# 3V3_LDO.net
KiCad netlist of a schematic drawn in Altium Designer
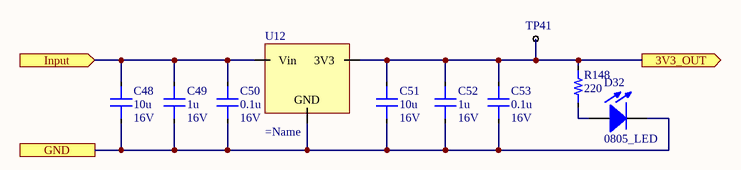
[diagram p0: 3V3_LDO.SchDoc]

(export (version "E")
  (design (tool "Eeschema 10.0.6"))
  (components
    (comp (ref "C48")
      (value "10u")
      (footprint "0805_CAP")
      (fields (field (name "VOLTAGE") "16V") (field (name "Comment") "Capacitor"))
      (libsource (lib "Capacitors") (part "Capacitor"))
    )
    (comp (ref "C49")
      (value "1u")
      (footprint "0603_CAP")
      (fields (field (name "VOLTAGE") "16V") (field (name "Comment") "Capacitor"))
      (libsource (lib "Capacitors") (part "Capacitor"))
    )
    (comp (ref "C50")
      (value "0.1u")
      (footprint "0805_CAP")
      (fields (field (name "VOLTAGE") "16V") (field (name "Comment") "Capacitor"))
      (libsource (lib "Capacitors") (part "Capacitor"))
    )
    (comp (ref "C51")
      (value "10u")
      (footprint "0805_CAP")
      (fields (field (name "VOLTAGE") "16V") (field (name "Comment") "Capacitor"))
      (libsource (lib "Capacitors") (part "Capacitor"))
    )
    (comp (ref "C52")
      (value "1u")
      (footprint "0805_CAP")
      (fields (field (name "VOLTAGE") "16V") (field (name "Comment") "Capacitor"))
      (libsource (lib "Capacitors") (part "Capacitor"))
    )
    (comp (ref "C53")
      (value "0.1u")
      (footprint "0805_CAP")
      (fields (field (name "VOLTAGE") "16V") (field (name "Comment") "Capacitor"))
      (libsource (lib "Capacitors") (part "Capacitor"))
    )
    (comp (ref "D32")
      (value "0805_LED")
      (footprint "0805_LED")
      (description "Generic 0805 LED")
      (libsource (lib "Diodes") (part "0805_LED"))
    )
    (comp (ref "R148")
      (value "220")
      (footprint "0603_RES")
      (fields (field (name "Comment") "Resistor"))
      (libsource (lib "Resistors") (part "Resistor"))
    )
    (comp (ref "TP41")
      (value "1mm Testpoint")
      (footprint "1mm_testpoint")
      (description "1mm test point")
      (libsource (lib "Connectors") (part "1mm Testpoint"))
    )
    (comp (ref "U12")
      (value "~")
      (footprint "DPAK3_TO-252-3")
      (description "IC REG LINEAR 3.3V 1A DPAK")
      (libsource (lib "Power") (part "NCP1117DT33T5G"))
    )
  )
  (nets
    (net (code "1") (name "/3V3_OUT") (class "Default")
      (node (ref "C51") (pin "2") (pinfunction "2_2") (pintype "passive"))
      (node (ref "C52") (pin "2") (pinfunction "2_2") (pintype "passive"))
      (node (ref "C53") (pin "2") (pinfunction "2_2") (pintype "passive"))
      (node (ref "R148") (pin "2") (pinfunction "2_2") (pintype "passive"))
      (node (ref "TP41") (pin "1") (pintype "passive"))
      (node (ref "U12") (pin "4") (pinfunction "3V3_4") (pintype "passive"))
    )
    (net (code "2") (name "/GND") (class "Default")
      (node (ref "C48") (pin "1") (pinfunction "1_1") (pintype "passive"))
      (node (ref "C49") (pin "1") (pinfunction "1_1") (pintype "passive"))
      (node (ref "C50") (pin "1") (pinfunction "1_1") (pintype "passive"))
      (node (ref "C51") (pin "1") (pinfunction "1_1") (pintype "passive"))
      (node (ref "C52") (pin "1") (pinfunction "1_1") (pintype "passive"))
      (node (ref "C53") (pin "1") (pinfunction "1_1") (pintype "passive"))
      (node (ref "D32") (pin "2") (pinfunction "K_2") (pintype "passive"))
      (node (ref "U12") (pin "1") (pinfunction "GND_1") (pintype "passive"))
    )
    (net (code "3") (name "/Input") (class "Default")
      (node (ref "C48") (pin "2") (pinfunction "2_2") (pintype "passive"))
      (node (ref "C49") (pin "2") (pinfunction "2_2") (pintype "passive"))
      (node (ref "C50") (pin "2") (pinfunction "2_2") (pintype "passive"))
      (node (ref "U12") (pin "3") (pinfunction "Vin_3") (pintype "passive"))
    )
    (net (code "4") (name "Net-(D32-A)") (class "Default")
      (node (ref "D32") (pin "1") (pinfunction "A_1") (pintype "passive"))
      (node (ref "R148") (pin "1") (pinfunction "1_1") (pintype "passive"))
    )
  )
)
